# untitled.net
KiCad netlist of a schematic drawn in EAGLE
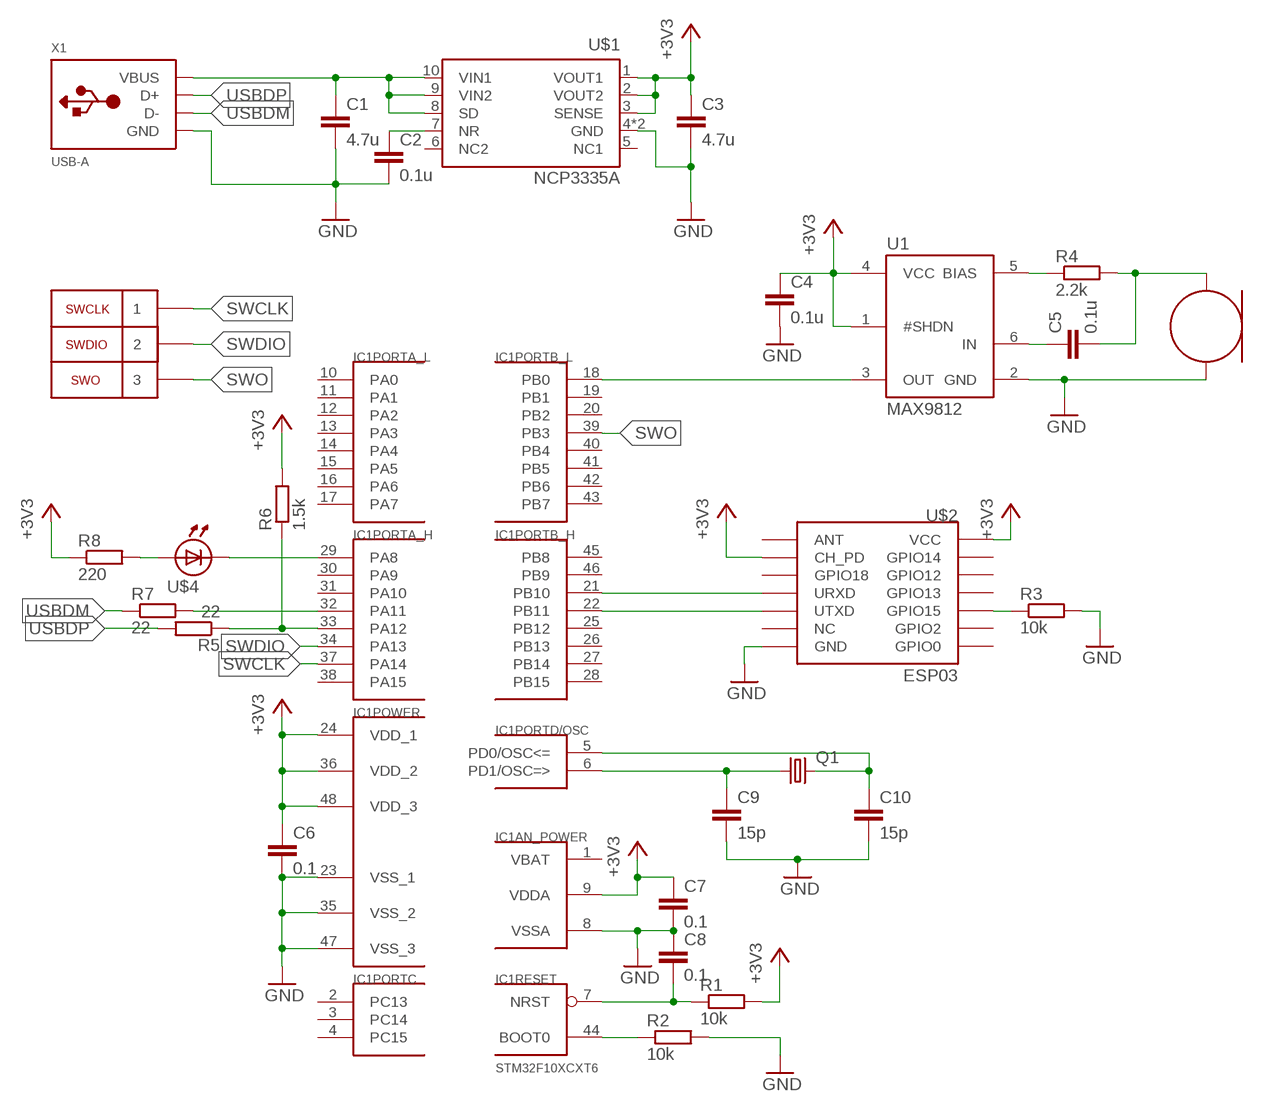
[diagram p0: schematic, sheet 1]

(export (version "E")
  (design (tool "Eeschema 10.0.6"))
  (components
    (comp (ref "C1")
      (value "4.7u")
      (footprint "eagle-import:C0805")
      (libsource (lib "eagle-import") (part "C-EUC0805"))
    )
    (comp (ref "C2")
      (value "0.1u")
      (footprint "eagle-import:C0805")
      (libsource (lib "eagle-import") (part "C-EUC0805"))
    )
    (comp (ref "C3")
      (value "4.7u")
      (footprint "eagle-import:C0805")
      (libsource (lib "eagle-import") (part "C-EUC0805"))
    )
    (comp (ref "C4")
      (value "0.1u")
      (footprint "eagle-import:C0603")
      (libsource (lib "eagle-import") (part "C-EUC0603"))
    )
    (comp (ref "C5")
      (value "0.1u")
      (footprint "eagle-import:C0603")
      (libsource (lib "eagle-import") (part "C-EUC0603"))
    )
    (comp (ref "C6")
      (value "0.1")
      (footprint "eagle-import:C0805")
      (libsource (lib "eagle-import") (part "C-EUC0805"))
    )
    (comp (ref "C7")
      (value "0.1")
      (footprint "eagle-import:C0805")
      (libsource (lib "eagle-import") (part "C-EUC0805"))
    )
    (comp (ref "C8")
      (value "0.1")
      (footprint "eagle-import:C0805")
      (libsource (lib "eagle-import") (part "C-EUC0805"))
    )
    (comp (ref "C9")
      (value "15p")
      (footprint "eagle-import:C0603")
      (libsource (lib "eagle-import") (part "C-EUC0603"))
    )
    (comp (ref "C10")
      (value "15p")
      (footprint "eagle-import:C0603")
      (libsource (lib "eagle-import") (part "C-EUC0603"))
    )
    (comp (ref "IC1")
      (value "STM32F10XCXT6")
      (footprint "eagle-import:TQFP48")
      (libsource (lib "eagle-import") (part "STM32F10XCXT6"))
    )
    (comp (ref "Q1")
      (value "CRYSTAL")
      (footprint "eagle-import:DSX321G")
      (libsource (lib "eagle-import") (part "CRYSTAL"))
    )
    (comp (ref "R1")
      (value "10k")
      (footprint "eagle-import:R0805")
      (libsource (lib "eagle-import") (part "R-EU_R0805"))
    )
    (comp (ref "R2")
      (value "10k")
      (footprint "eagle-import:R0805")
      (libsource (lib "eagle-import") (part "R-EU_R0805"))
    )
    (comp (ref "R3")
      (value "10k")
      (footprint "eagle-import:R0805")
      (libsource (lib "eagle-import") (part "R-EU_R0805"))
    )
    (comp (ref "R4")
      (value "2.2k")
      (footprint "eagle-import:R0603")
      (libsource (lib "eagle-import") (part "R-EU_R0603"))
    )
    (comp (ref "R5")
      (value "22")
      (footprint "eagle-import:R0805")
      (libsource (lib "eagle-import") (part "R-EU_R0805"))
    )
    (comp (ref "R6")
      (value "1.5k")
      (footprint "eagle-import:R0805")
      (libsource (lib "eagle-import") (part "R-EU_R0805"))
    )
    (comp (ref "R7")
      (value "22")
      (footprint "eagle-import:R0805")
      (libsource (lib "eagle-import") (part "R-EU_R0805"))
    )
    (comp (ref "R8")
      (value "220")
      (footprint "eagle-import:R0805")
      (libsource (lib "eagle-import") (part "R-EU_R0805"))
    )
    (comp (ref "U$1")
      (value "NCP3335A")
      (footprint "eagle-import:DFN10-3X3")
      (libsource (lib "eagle-import") (part "NCP3335A"))
    )
    (comp (ref "U$2")
      (value "ESP03")
      (footprint "eagle-import:ESP03")
      (libsource (lib "eagle-import") (part "ESP03"))
    )
    (comp (ref "U$3")
      (value "MIC")
      (footprint "eagle-import:MIC")
      (libsource (lib "eagle-import") (part "MIC"))
    )
    (comp (ref "U$4")
      (value "LED1206")
      (footprint "eagle-import:R1206")
      (libsource (lib "eagle-import") (part "LED1206"))
    )
    (comp (ref "U$5")
      (value "PLS2-3")
      (footprint "eagle-import:PLS2-3")
      (libsource (lib "eagle-import") (part "PLS2-3"))
    )
    (comp (ref "U1")
      (value "MAX9812")
      (footprint "eagle-import:SC-70-6")
      (libsource (lib "eagle-import") (part "MAX9812"))
    )
    (comp (ref "X1")
      (value "USB-A")
      (footprint "eagle-import:MOLEX_480371000")
      (libsource (lib "eagle-import") (part "USB-A"))
    )
  )
  (nets
    (net (code "1") (name "+3V3") (class "Default")
      (node (ref "C3") (pin "1") (pinfunction "1_1") (pintype "passive"))
      (node (ref "C4") (pin "1") (pinfunction "1_1") (pintype "passive"))
      (node (ref "C6") (pin "1") (pinfunction "1_1") (pintype "passive"))
      (node (ref "C7") (pin "1") (pinfunction "1_1") (pintype "passive"))
      (node (ref "IC1") (pin "24") (pinfunction "VDD_1_24") (pintype "power_in"))
      (node (ref "IC1") (pin "36") (pinfunction "VDD_2_36") (pintype "power_in"))
      (node (ref "IC1") (pin "48") (pinfunction "VDD_3_48") (pintype "power_in"))
      (node (ref "IC1") (pin "9") (pinfunction "VDDA_9") (pintype "power_in"))
      (node (ref "R1") (pin "2") (pinfunction "2_2") (pintype "passive"))
      (node (ref "R6") (pin "2") (pinfunction "2_2") (pintype "passive"))
      (node (ref "R8") (pin "1") (pinfunction "1_1") (pintype "passive"))
      (node (ref "U$1") (pin "1") (pinfunction "VOUT1_1") (pintype "bidirectional"))
      (node (ref "U$1") (pin "2") (pinfunction "VOUT2_2") (pintype "bidirectional"))
      (node (ref "U$1") (pin "3") (pinfunction "SENSE_3") (pintype "power_in"))
      (node (ref "U$2") (pin "CH_PD") (pinfunction "CH_PD_CH_PD") (pintype "bidirectional"))
      (node (ref "U$2") (pin "VCC") (pinfunction "VCC_VCC") (pintype "bidirectional"))
      (node (ref "U1") (pin "1") (pinfunction "#SHDN_1") (pintype "input"))
      (node (ref "U1") (pin "4") (pinfunction "VCC_4") (pintype "power_in"))
    )
    (net (code "2") (name "/VBAT") (class "Default")
      (node (ref "IC1") (pin "1") (pinfunction "VBAT_1") (pintype "power_in"))
    )
    (net (code "3") (name "GND") (class "Default")
      (node (ref "C1") (pin "2") (pinfunction "2_2") (pintype "passive"))
      (node (ref "C10") (pin "2") (pinfunction "2_2") (pintype "passive"))
      (node (ref "C2") (pin "2") (pinfunction "2_2") (pintype "passive"))
      (node (ref "C3") (pin "2") (pinfunction "2_2") (pintype "passive"))
      (node (ref "C4") (pin "2") (pinfunction "2_2") (pintype "passive"))
      (node (ref "C6") (pin "2") (pinfunction "2_2") (pintype "passive"))
      (node (ref "C7") (pin "2") (pinfunction "2_2") (pintype "passive"))
      (node (ref "C8") (pin "1") (pinfunction "1_1") (pintype "passive"))
      (node (ref "C9") (pin "2") (pinfunction "2_2") (pintype "passive"))
      (node (ref "IC1") (pin "23") (pinfunction "VSS_1_23") (pintype "power_in"))
      (node (ref "IC1") (pin "35") (pinfunction "VSS_2_35") (pintype "power_in"))
      (node (ref "IC1") (pin "47") (pinfunction "VSS_3_47") (pintype "power_in"))
      (node (ref "IC1") (pin "8") (pinfunction "VSSA_8") (pintype "power_in"))
      (node (ref "R2") (pin "2") (pinfunction "2_2") (pintype "passive"))
      (node (ref "R3") (pin "2") (pinfunction "2_2") (pintype "passive"))
      (node (ref "U$1") (pin "4") (pinfunction "GND_4") (pintype "power_in"))
      (node (ref "U$1") (pin "EXP") (pinfunction "GND_EXP") (pintype "power_in"))
      (node (ref "U$2") (pin "GND") (pinfunction "GND_GND") (pintype "bidirectional"))
      (node (ref "U$3") (pin "P$2") (pinfunction "P$2_P$2") (pintype "bidirectional"))
      (node (ref "U1") (pin "2") (pinfunction "GND_2") (pintype "power_in"))
      (node (ref "X1") (pin "4") (pinfunction "GND_4") (pintype "power_in"))
    )
    (net (code "4") (name "Net-(C5-Pad2)") (class "Default")
      (node (ref "C5") (pin "2") (pinfunction "2_2") (pintype "passive"))
      (node (ref "R4") (pin "2") (pinfunction "2_2") (pintype "passive"))
      (node (ref "U$3") (pin "P$1") (pinfunction "P$1_P$1") (pintype "bidirectional"))
    )
    (net (code "5") (name "Net-(IC1B-PA8)") (class "Default")
      (node (ref "IC1") (pin "29") (pinfunction "PA8_29") (pintype "bidirectional"))
      (node (ref "U$4") (pin "2") (pinfunction "P$2_2") (pintype "bidirectional"))
    )
    (net (code "6") (name "Net-(IC1B-PA11)") (class "Default")
      (node (ref "IC1") (pin "32") (pinfunction "PA11_32") (pintype "bidirectional"))
      (node (ref "R7") (pin "2") (pinfunction "2_2") (pintype "passive"))
    )
    (net (code "7") (name "Net-(IC1B-PA12)") (class "Default")
      (node (ref "IC1") (pin "33") (pinfunction "PA12_33") (pintype "bidirectional"))
      (node (ref "R5") (pin "1") (pinfunction "1_1") (pintype "passive"))
      (node (ref "R6") (pin "1") (pinfunction "1_1") (pintype "passive"))
    )
    (net (code "8") (name "Net-(IC1D-PB10)") (class "Default")
      (node (ref "IC1") (pin "21") (pinfunction "PB10_21") (pintype "bidirectional"))
      (node (ref "U$2") (pin "URXD") (pinfunction "URXD_URXD") (pintype "bidirectional"))
    )
    (net (code "9") (name "Net-(IC1D-PB11)") (class "Default")
      (node (ref "IC1") (pin "22") (pinfunction "PB11_22") (pintype "bidirectional"))
      (node (ref "U$2") (pin "UTXD") (pinfunction "UTXD_UTXD") (pintype "bidirectional"))
    )
    (net (code "10") (name "Net-(IC1E-PB0)") (class "Default")
      (node (ref "IC1") (pin "18") (pinfunction "PB0_18") (pintype "bidirectional"))
      (node (ref "U1") (pin "3") (pinfunction "OUT_3") (pintype "output"))
    )
    (net (code "11") (name "Net-(IC1G-PD0{slash}OSC<=)") (class "Default")
      (node (ref "C10") (pin "1") (pinfunction "1_1") (pintype "passive"))
      (node (ref "IC1") (pin "5") (pinfunction "PD0/OSC<=_5") (pintype "bidirectional"))
      (node (ref "Q1") (pin "P$3") (pinfunction "2_P$3") (pintype "passive"))
    )
    (net (code "12") (name "Net-(IC1G-PD1{slash}OSC=>)") (class "Default")
      (node (ref "C9") (pin "1") (pinfunction "1_1") (pintype "passive"))
      (node (ref "IC1") (pin "6") (pinfunction "PD1/OSC=>_6") (pintype "bidirectional"))
      (node (ref "Q1") (pin "P$1") (pinfunction "1_P$1") (pintype "passive"))
    )
    (net (code "13") (name "Net-(IC1I-BOOT0)") (class "Default")
      (node (ref "IC1") (pin "44") (pinfunction "BOOT0_44") (pintype "input"))
      (node (ref "R2") (pin "1") (pinfunction "1_1") (pintype "passive"))
    )
    (net (code "14") (name "Net-(IC1I-NRST)") (class "Default")
      (node (ref "C8") (pin "2") (pinfunction "2_2") (pintype "passive"))
      (node (ref "IC1") (pin "7") (pinfunction "NRST_7") (pintype "input"))
      (node (ref "R1") (pin "1") (pinfunction "1_1") (pintype "passive"))
    )
    (net (code "15") (name "Net-(R3-Pad1)") (class "Default")
      (node (ref "R3") (pin "1") (pinfunction "1_1") (pintype "passive"))
      (node (ref "U$2") (pin "GPIO15") (pinfunction "GPIO15_GPIO15") (pintype "bidirectional"))
    )
    (net (code "16") (name "Net-(U$1-NR)") (class "Default")
      (node (ref "C2") (pin "1") (pinfunction "1_1") (pintype "passive"))
      (node (ref "U$1") (pin "7") (pinfunction "NR_7") (pintype "input"))
    )
    (net (code "17") (name "Net-(U$1-SD)") (class "Default")
      (node (ref "C1") (pin "1") (pinfunction "1_1") (pintype "passive"))
      (node (ref "U$1") (pin "10") (pinfunction "VIN1_10") (pintype "input"))
      (node (ref "U$1") (pin "8") (pinfunction "SD_8") (pintype "power_in"))
      (node (ref "U$1") (pin "9") (pinfunction "VIN2_9") (pintype "power_in"))
      (node (ref "X1") (pin "1") (pinfunction "VBUS_1") (pintype "power_in"))
    )
    (net (code "18") (name "Net-(U$4-P$1)") (class "Default")
      (node (ref "R8") (pin "2") (pinfunction "2_2") (pintype "passive"))
      (node (ref "U$4") (pin "1") (pinfunction "P$1_1") (pintype "bidirectional"))
    )
    (net (code "19") (name "Net-(U1-BIAS)") (class "Default")
      (node (ref "R4") (pin "1") (pinfunction "1_1") (pintype "passive"))
      (node (ref "U1") (pin "5") (pinfunction "BIAS_5") (pintype "input"))
    )
    (net (code "20") (name "Net-(U1-IN)") (class "Default")
      (node (ref "C5") (pin "1") (pinfunction "1_1") (pintype "passive"))
      (node (ref "U1") (pin "6") (pinfunction "IN_6") (pintype "input"))
    )
    (net (code "21") (name "SWCLK") (class "Default")
      (node (ref "IC1") (pin "37") (pinfunction "PA14_37") (pintype "bidirectional"))
      (node (ref "U$5") (pin "P$1") (pinfunction "1_P$1") (pintype "bidirectional"))
    )
    (net (code "22") (name "SWDIO") (class "Default")
      (node (ref "IC1") (pin "34") (pinfunction "PA13_34") (pintype "bidirectional"))
      (node (ref "U$5") (pin "P$2") (pinfunction "2_P$2") (pintype "bidirectional"))
    )
    (net (code "23") (name "SWO") (class "Default")
      (node (ref "IC1") (pin "39") (pinfunction "PB3_39") (pintype "bidirectional"))
      (node (ref "U$5") (pin "P$3") (pinfunction "3_P$3") (pintype "bidirectional"))
    )
    (net (code "24") (name "USBDM") (class "Default")
      (node (ref "R7") (pin "1") (pinfunction "1_1") (pintype "passive"))
      (node (ref "X1") (pin "2") (pinfunction "D-_2") (pintype "bidirectional"))
    )
    (net (code "25") (name "USBDP") (class "Default")
      (node (ref "R5") (pin "2") (pinfunction "2_2") (pintype "passive"))
      (node (ref "X1") (pin "3") (pinfunction "D+_3") (pintype "bidirectional"))
    )
    (net (code "26") (name "unconnected-(IC1B-PA9-Pad30)") (class "Default")
      (node (ref "IC1") (pin "30") (pinfunction "PA9_30") (pintype "bidirectional"))
    )
    (net (code "27") (name "unconnected-(IC1B-PA10-Pad31)") (class "Default")
      (node (ref "IC1") (pin "31") (pinfunction "PA10_31") (pintype "bidirectional"))
    )
    (net (code "28") (name "unconnected-(IC1B-PA15-Pad38)") (class "Default")
      (node (ref "IC1") (pin "38") (pinfunction "PA15_38") (pintype "bidirectional"))
    )
    (net (code "29") (name "unconnected-(IC1C-PA0-Pad10)") (class "Default")
      (node (ref "IC1") (pin "10") (pinfunction "PA0_10") (pintype "bidirectional"))
    )
    (net (code "30") (name "unconnected-(IC1C-PA1-Pad11)") (class "Default")
      (node (ref "IC1") (pin "11") (pinfunction "PA1_11") (pintype "bidirectional"))
    )
    (net (code "31") (name "unconnected-(IC1C-PA2-Pad12)") (class "Default")
      (node (ref "IC1") (pin "12") (pinfunction "PA2_12") (pintype "bidirectional"))
    )
    (net (code "32") (name "unconnected-(IC1C-PA3-Pad13)") (class "Default")
      (node (ref "IC1") (pin "13") (pinfunction "PA3_13") (pintype "bidirectional"))
    )
    (net (code "33") (name "unconnected-(IC1C-PA4-Pad14)") (class "Default")
      (node (ref "IC1") (pin "14") (pinfunction "PA4_14") (pintype "bidirectional"))
    )
    (net (code "34") (name "unconnected-(IC1C-PA5-Pad15)") (class "Default")
      (node (ref "IC1") (pin "15") (pinfunction "PA5_15") (pintype "bidirectional"))
    )
    (net (code "35") (name "unconnected-(IC1C-PA6-Pad16)") (class "Default")
      (node (ref "IC1") (pin "16") (pinfunction "PA6_16") (pintype "bidirectional"))
    )
    (net (code "36") (name "unconnected-(IC1C-PA7-Pad17)") (class "Default")
      (node (ref "IC1") (pin "17") (pinfunction "PA7_17") (pintype "bidirectional"))
    )
    (net (code "37") (name "unconnected-(IC1D-PB8-Pad45)") (class "Default")
      (node (ref "IC1") (pin "45") (pinfunction "PB8_45") (pintype "bidirectional"))
    )
    (net (code "38") (name "unconnected-(IC1D-PB9-Pad46)") (class "Default")
      (node (ref "IC1") (pin "46") (pinfunction "PB9_46") (pintype "bidirectional"))
    )
    (net (code "39") (name "unconnected-(IC1D-PB12-Pad25)") (class "Default")
      (node (ref "IC1") (pin "25") (pinfunction "PB12_25") (pintype "bidirectional"))
    )
    (net (code "40") (name "unconnected-(IC1D-PB13-Pad26)") (class "Default")
      (node (ref "IC1") (pin "26") (pinfunction "PB13_26") (pintype "bidirectional"))
    )
    (net (code "41") (name "unconnected-(IC1D-PB14-Pad27)") (class "Default")
      (node (ref "IC1") (pin "27") (pinfunction "PB14_27") (pintype "bidirectional"))
    )
    (net (code "42") (name "unconnected-(IC1D-PB15-Pad28)") (class "Default")
      (node (ref "IC1") (pin "28") (pinfunction "PB15_28") (pintype "bidirectional"))
    )
    (net (code "43") (name "unconnected-(IC1E-PB1-Pad19)") (class "Default")
      (node (ref "IC1") (pin "19") (pinfunction "PB1_19") (pintype "bidirectional"))
    )
    (net (code "44") (name "unconnected-(IC1E-PB2-Pad20)") (class "Default")
      (node (ref "IC1") (pin "20") (pinfunction "PB2_20") (pintype "bidirectional"))
    )
    (net (code "45") (name "unconnected-(IC1E-PB4-Pad40)") (class "Default")
      (node (ref "IC1") (pin "40") (pinfunction "PB4_40") (pintype "bidirectional"))
    )
    (net (code "46") (name "unconnected-(IC1E-PB5-Pad41)") (class "Default")
      (node (ref "IC1") (pin "41") (pinfunction "PB5_41") (pintype "bidirectional"))
    )
    (net (code "47") (name "unconnected-(IC1E-PB6-Pad42)") (class "Default")
      (node (ref "IC1") (pin "42") (pinfunction "PB6_42") (pintype "bidirectional"))
    )
    (net (code "48") (name "unconnected-(IC1E-PB7-Pad43)") (class "Default")
      (node (ref "IC1") (pin "43") (pinfunction "PB7_43") (pintype "bidirectional"))
    )
    (net (code "49") (name "unconnected-(IC1F-PC13-Pad2)") (class "Default")
      (node (ref "IC1") (pin "2") (pinfunction "PC13_2") (pintype "bidirectional"))
    )
    (net (code "50") (name "unconnected-(IC1F-PC14-Pad3)") (class "Default")
      (node (ref "IC1") (pin "3") (pinfunction "PC14_3") (pintype "bidirectional"))
    )
    (net (code "51") (name "unconnected-(IC1F-PC15-Pad4)") (class "Default")
      (node (ref "IC1") (pin "4") (pinfunction "PC15_4") (pintype "bidirectional"))
    )
    (net (code "52") (name "unconnected-(U$1-NC1-Pad5)") (class "Default")
      (node (ref "U$1") (pin "5") (pinfunction "NC1_5") (pintype "input"))
    )
    (net (code "53") (name "unconnected-(U$1-NC2-Pad6)") (class "Default")
      (node (ref "U$1") (pin "6") (pinfunction "NC2_6") (pintype "input"))
    )
    (net (code "54") (name "unconnected-(U$2-PadANT)") (class "Default")
      (node (ref "U$2") (pin "ANT") (pinfunction "ANT_ANT") (pintype "bidirectional"))
    )
    (net (code "55") (name "unconnected-(U$2-PadGPIO0)") (class "Default")
      (node (ref "U$2") (pin "GPIO0") (pinfunction "GPIO0_GPIO0") (pintype "bidirectional"))
    )
    (net (code "56") (name "unconnected-(U$2-PadGPIO2)") (class "Default")
      (node (ref "U$2") (pin "GPIO2") (pinfunction "GPIO2_GPIO2") (pintype "bidirectional"))
    )
    (net (code "57") (name "unconnected-(U$2-PadGPIO12)") (class "Default")
      (node (ref "U$2") (pin "GPIO12") (pinfunction "GPIO12_GPIO12") (pintype "bidirectional"))
    )
    (net (code "58") (name "unconnected-(U$2-PadGPIO13)") (class "Default")
      (node (ref "U$2") (pin "GPIO13") (pinfunction "GPIO13_GPIO13") (pintype "bidirectional"))
    )
    (net (code "59") (name "unconnected-(U$2-PadGPIO14)") (class "Default")
      (node (ref "U$2") (pin "GPIO14") (pinfunction "GPIO14_GPIO14") (pintype "bidirectional"))
    )
    (net (code "60") (name "unconnected-(U$2-PadGPIO18)") (class "Default")
      (node (ref "U$2") (pin "GPIO18") (pinfunction "GPIO18_GPIO18") (pintype "bidirectional"))
    )
    (net (code "61") (name "unconnected-(U$2-PadNC)") (class "Default")
      (node (ref "U$2") (pin "NC") (pinfunction "NC_NC") (pintype "bidirectional"))
    )
  )
)
